# 2TinyISD1700_V2_2020-08-10-smd-sop.net
KiCad netlist of a schematic drawn in EAGLE
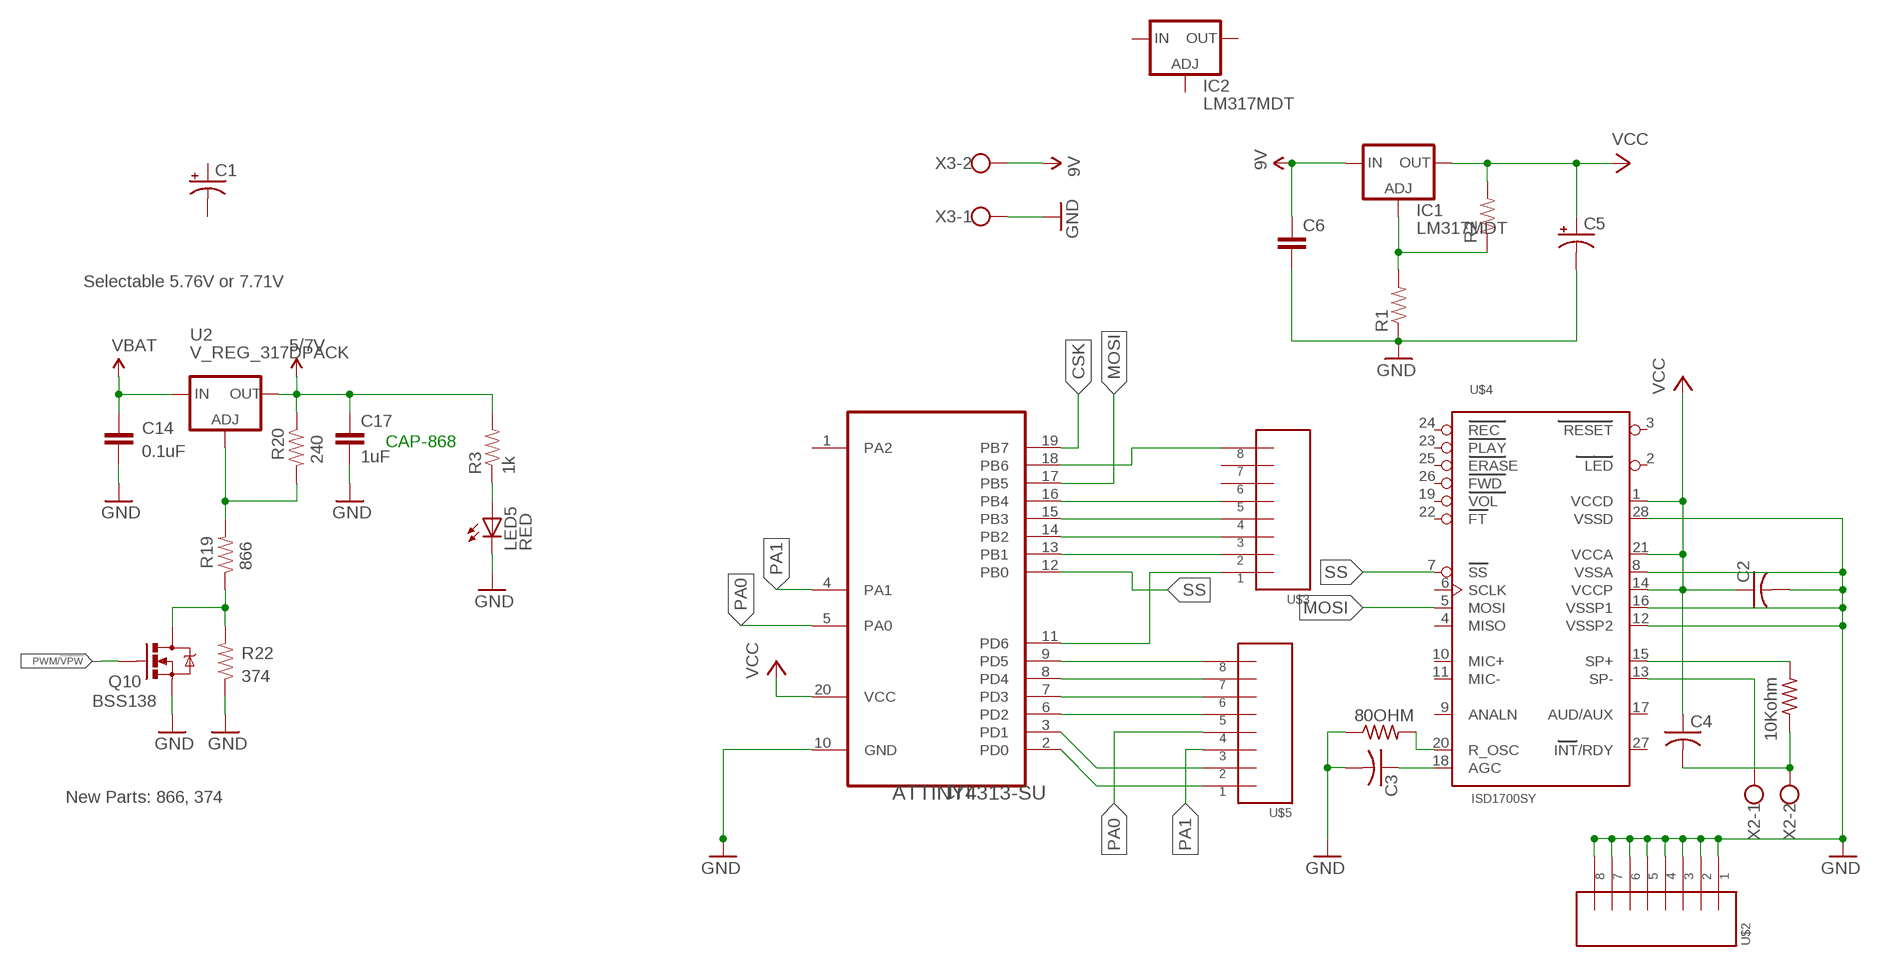
[diagram p0: schematic, sheet 1]

(export (version "E")
  (design (tool "Eeschema 10.0.6"))
  (components
    (comp (ref "80OHM")
      (value "R-US_0204/2V")
      (footprint "eagle-import:0204V")
      (libsource (lib "eagle-import") (part "R-US_0204/2V"))
    )
    (comp (ref "80OHM1")
      (value "10Kohm")
      (footprint "eagle-import:0204V")
      (libsource (lib "eagle-import") (part "R-US_0204/2V"))
    )
    (comp (ref "C1")
      (value "CAP_POL1206")
      (footprint "eagle-import:EIA3216")
      (libsource (lib "eagle-import") (part "CAP_POL1206"))
    )
    (comp (ref "C2")
      (value "C-US050-030X075")
      (footprint "eagle-import:C050-030X075")
      (libsource (lib "eagle-import") (part "C-US050-030X075"))
    )
    (comp (ref "C3")
      (value "C-US050-030X075")
      (footprint "eagle-import:C050-030X075")
      (libsource (lib "eagle-import") (part "C-US050-030X075"))
    )
    (comp (ref "C4")
      (value "C-US050-030X075")
      (footprint "eagle-import:C050-030X075")
      (libsource (lib "eagle-import") (part "C-US050-030X075"))
    )
    (comp (ref "C5")
      (value "CAP_POL1206")
      (footprint "eagle-import:EIA3216")
      (libsource (lib "eagle-import") (part "CAP_POL1206"))
    )
    (comp (ref "C6")
      (value "CAP0805")
      (footprint "eagle-import:0805")
      (libsource (lib "eagle-import") (part "SparkFun2_CAP0805"))
    )
    (comp (ref "C14")
      (value "0.1uF")
      (footprint "eagle-import:0402-CAP")
      (libsource (lib "eagle-import") (part "CAP0402-CAP"))
    )
    (comp (ref "C17")
      (value "1uF")
      (footprint "eagle-import:0402-CAP")
      (libsource (lib "eagle-import") (part "CAP0402-CAP"))
    )
    (comp (ref "IC1")
      (value "LM317MDT")
      (footprint "eagle-import:DPACK")
      (libsource (lib "eagle-import") (part "LM317?MDT"))
    )
    (comp (ref "IC2")
      (value "LM317MDT")
      (footprint "eagle-import:DPACK")
      (libsource (lib "eagle-import") (part "LM317?MDT"))
    )
    (comp (ref "LED5")
      (value "RED")
      (footprint "eagle-import:LED-0603")
      (libsource (lib "eagle-import") (part "LED0603"))
    )
    (comp (ref "Q10")
      (value "BSS138")
      (footprint "eagle-import:SOT23-3")
      (libsource (lib "eagle-import") (part "MOSFET-NCHANNELSMD"))
    )
    (comp (ref "R1")
      (value "RESISTOR")
      (footprint "eagle-import:0805")
      (libsource (lib "eagle-import") (part "RESISTOR"))
    )
    (comp (ref "R2")
      (value "RESISTOR")
      (footprint "eagle-import:0805")
      (libsource (lib "eagle-import") (part "RESISTOR"))
    )
    (comp (ref "R3")
      (value "1k")
      (footprint "eagle-import:0402-RES")
      (libsource (lib "eagle-import") (part "RESISTOR0402-RES"))
    )
    (comp (ref "R19")
      (value "866")
      (footprint "eagle-import:0402-RES")
      (libsource (lib "eagle-import") (part "RESISTOR0402-RES"))
    )
    (comp (ref "R20")
      (value "240")
      (footprint "eagle-import:0402-RES")
      (libsource (lib "eagle-import") (part "RESISTOR0402-RES"))
    )
    (comp (ref "R22")
      (value "374")
      (footprint "eagle-import:0402-RES")
      (libsource (lib "eagle-import") (part "RESISTOR0402-RES"))
    )
    (comp (ref "U$2")
      (value "8PIN_HEADER")
      (footprint "eagle-import:8PIN_HEADER")
      (fields (field (name "MF") "RENESAS") (field (name "MPN") "YSDKS128E10"))
      (libsource (lib "eagle-import") (part "8PIN_HEADER"))
    )
    (comp (ref "U$3")
      (value "8PIN_HEADER")
      (footprint "eagle-import:8PIN_HEADER")
      (fields (field (name "MF") "RENESAS") (field (name "MPN") "YSDKS128E10"))
      (libsource (lib "eagle-import") (part "8PIN_HEADER"))
    )
    (comp (ref "U$4")
      (value "ISD1700SY")
      (footprint "eagle-import:SO28W")
      (libsource (lib "eagle-import") (part "ISD1700SY"))
    )
    (comp (ref "U$5")
      (value "8PIN_HEADER")
      (footprint "eagle-import:8PIN_HEADER")
      (fields (field (name "MF") "RENESAS") (field (name "MPN") "YSDKS128E10"))
      (libsource (lib "eagle-import") (part "8PIN_HEADER"))
    )
    (comp (ref "U1")
      (value "ATTINY4313-SU")
      (footprint "eagle-import:SOIC127P1032X265-20N")
      (fields (field (name "MF") "MICROCHIP"))
      (libsource (lib "eagle-import") (part "ATTINY4313-SU"))
    )
    (comp (ref "U2")
      (value "V_REG_317DPACK")
      (footprint "eagle-import:V-REG_DPACK")
      (libsource (lib "eagle-import") (part "V_REG_317DPACK"))
    )
    (comp (ref "X2")
      (value "W237-102")
      (footprint "eagle-import:W237-102")
      (fields (field (name "MPN") "237-102"))
      (libsource (lib "eagle-import") (part "W237-102"))
    )
    (comp (ref "X3")
      (value "W237-102")
      (footprint "eagle-import:W237-102")
      (fields (field (name "MPN") "237-102") (field (name "OC_NEWARK") "70K9898"))
      (libsource (lib "eagle-import") (part "W237-102"))
    )
  )
  (nets
    (net (code "1") (name "/PWM{slash}~{VPW}") (class "Default")
      (node (ref "Q10") (pin "1") (pinfunction "G_1") (pintype "passive"))
    )
    (net (code "2") (name "5{slash}7V") (class "Default")
      (node (ref "C17") (pin "1") (pinfunction "1_1") (pintype "passive"))
      (node (ref "C2") (pin "1") (pinfunction "1_1") (pintype "passive"))
      (node (ref "C4") (pin "1") (pinfunction "1_1") (pintype "passive"))
      (node (ref "C5") (pin "A") (pinfunction "+_A") (pintype "passive"))
      (node (ref "IC1") (pin "4") (pinfunction "OUT_4") (pintype "passive"))
      (node (ref "R2") (pin "2") (pinfunction "2_2") (pintype "passive"))
      (node (ref "R20") (pin "1") (pinfunction "1_1") (pintype "passive"))
      (node (ref "R3") (pin "2") (pinfunction "2_2") (pintype "passive"))
      (node (ref "U$4") (pin "1") (pinfunction "VCCD_1") (pintype "power_in"))
      (node (ref "U$4") (pin "14") (pinfunction "VCCP_14") (pintype "power_in"))
      (node (ref "U$4") (pin "21") (pinfunction "VCCA_21") (pintype "power_in"))
      (node (ref "U1") (pin "20") (pinfunction "VCC_20") (pintype "power_in"))
      (node (ref "U2") (pin "4") (pinfunction "OUT_4") (pintype "output"))
    )
    (net (code "3") (name "9V") (class "Default")
      (node (ref "C6") (pin "1") (pinfunction "1_1") (pintype "passive"))
      (node (ref "IC1") (pin "3") (pinfunction "IN_3") (pintype "input"))
      (node (ref "X3") (pin "2") (pinfunction "KL_2") (pintype "passive"))
    )
    (net (code "4") (name "CSK") (class "Default")
      (node (ref "U1") (pin "19") (pinfunction "PB7_19") (pintype "bidirectional"))
    )
    (net (code "5") (name "GND") (class "Default")
      (node (ref "80OHM") (pin "1") (pinfunction "1_1") (pintype "passive"))
      (node (ref "C14") (pin "2") (pinfunction "2_2") (pintype "passive"))
      (node (ref "C17") (pin "2") (pinfunction "2_2") (pintype "passive"))
      (node (ref "C2") (pin "2") (pinfunction "2_2") (pintype "passive"))
      (node (ref "C3") (pin "2") (pinfunction "2_2") (pintype "passive"))
      (node (ref "C5") (pin "C") (pinfunction "-_C") (pintype "passive"))
      (node (ref "C6") (pin "2") (pinfunction "2_2") (pintype "passive"))
      (node (ref "LED5") (pin "C") (pinfunction "C_C") (pintype "passive"))
      (node (ref "Q10") (pin "2") (pinfunction "S_2") (pintype "passive"))
      (node (ref "R1") (pin "1") (pinfunction "1_1") (pintype "passive"))
      (node (ref "R22") (pin "1") (pinfunction "1_1") (pintype "passive"))
      (node (ref "U$2") (pin "P$1") (pinfunction "P$1_P$1") (pintype "bidirectional"))
      (node (ref "U$2") (pin "P$2") (pinfunction "P$2_P$2") (pintype "bidirectional"))
      (node (ref "U$2") (pin "P$3") (pinfunction "P$3_P$3") (pintype "bidirectional"))
      (node (ref "U$2") (pin "P$4") (pinfunction "P$4_P$4") (pintype "bidirectional"))
      (node (ref "U$2") (pin "P$5") (pinfunction "P$5_P$5") (pintype "bidirectional"))
      (node (ref "U$2") (pin "P$6") (pinfunction "P$6_P$6") (pintype "bidirectional"))
      (node (ref "U$2") (pin "P$7") (pinfunction "P$7_P$7") (pintype "bidirectional"))
      (node (ref "U$2") (pin "P$8") (pinfunction "P$8_P$8") (pintype "bidirectional"))
      (node (ref "U$4") (pin "12") (pinfunction "VSSP2_12") (pintype "power_in"))
      (node (ref "U$4") (pin "16") (pinfunction "VSSP1_16") (pintype "power_in"))
      (node (ref "U$4") (pin "28") (pinfunction "VSSD_28") (pintype "power_in"))
      (node (ref "U$4") (pin "8") (pinfunction "VSSA_8") (pintype "power_in"))
      (node (ref "U1") (pin "10") (pinfunction "GND_10") (pintype "passive"))
      (node (ref "X3") (pin "1") (pinfunction "KL_1") (pintype "passive"))
    )
    (net (code "6") (name "MOSI") (class "Default")
      (node (ref "U$4") (pin "5") (pinfunction "MOSI_5") (pintype "input"))
      (node (ref "U1") (pin "17") (pinfunction "PB5_17") (pintype "bidirectional"))
    )
    (net (code "7") (name "Net-(IC1-ADJ)") (class "Default")
      (node (ref "IC1") (pin "1") (pinfunction "ADJ_1") (pintype "input"))
      (node (ref "R1") (pin "2") (pinfunction "2_2") (pintype "passive"))
      (node (ref "R2") (pin "1") (pinfunction "1_1") (pintype "passive"))
    )
    (net (code "8") (name "Net-(LED5-PadA)") (class "Default")
      (node (ref "LED5") (pin "A") (pinfunction "A_A") (pintype "passive"))
      (node (ref "R3") (pin "1") (pinfunction "1_1") (pintype "passive"))
    )
    (net (code "9") (name "Net-(Q10-D)") (class "Default")
      (node (ref "Q10") (pin "3") (pinfunction "D_3") (pintype "passive"))
      (node (ref "R19") (pin "1") (pinfunction "1_1") (pintype "passive"))
      (node (ref "R22") (pin "2") (pinfunction "2_2") (pintype "passive"))
    )
    (net (code "10") (name "Net-(U$4-AGC)") (class "Default")
      (node (ref "C3") (pin "1") (pinfunction "1_1") (pintype "passive"))
      (node (ref "U$4") (pin "18") (pinfunction "AGC_18") (pintype "passive"))
    )
    (net (code "11") (name "Net-(U$4-R_OSC)") (class "Default")
      (node (ref "80OHM") (pin "2") (pinfunction "2_2") (pintype "passive"))
      (node (ref "U$4") (pin "20") (pinfunction "R_OSC_20") (pintype "passive"))
    )
    (net (code "12") (name "Net-(U$4-SP+)") (class "Default")
      (node (ref "80OHM1") (pin "2") (pinfunction "2_2") (pintype "passive"))
      (node (ref "U$4") (pin "15") (pinfunction "SP+_15") (pintype "output"))
    )
    (net (code "13") (name "Net-(U$4-SP-)") (class "Default")
      (node (ref "U$4") (pin "13") (pinfunction "SP-_13") (pintype "output"))
      (node (ref "X2") (pin "1") (pinfunction "KL_1") (pintype "passive"))
    )
    (net (code "14") (name "Net-(U1-PB1)") (class "Default")
      (node (ref "U$3") (pin "P$2") (pinfunction "P$2_P$2") (pintype "bidirectional"))
      (node (ref "U1") (pin "13") (pinfunction "PB1_13") (pintype "bidirectional"))
    )
    (net (code "15") (name "Net-(U1-PB2)") (class "Default")
      (node (ref "U$3") (pin "P$3") (pinfunction "P$3_P$3") (pintype "bidirectional"))
      (node (ref "U1") (pin "14") (pinfunction "PB2_14") (pintype "bidirectional"))
    )
    (net (code "16") (name "Net-(U1-PB3)") (class "Default")
      (node (ref "U$3") (pin "P$4") (pinfunction "P$4_P$4") (pintype "bidirectional"))
      (node (ref "U1") (pin "15") (pinfunction "PB3_15") (pintype "bidirectional"))
    )
    (net (code "17") (name "Net-(U1-PB4)") (class "Default")
      (node (ref "U$3") (pin "P$5") (pinfunction "P$5_P$5") (pintype "bidirectional"))
      (node (ref "U1") (pin "16") (pinfunction "PB4_16") (pintype "bidirectional"))
    )
    (net (code "18") (name "Net-(U1-PB6)") (class "Default")
      (node (ref "U$3") (pin "P$8") (pinfunction "P$8_P$8") (pintype "bidirectional"))
      (node (ref "U1") (pin "18") (pinfunction "PB6_18") (pintype "bidirectional"))
    )
    (net (code "19") (name "Net-(U1-PD0)") (class "Default")
      (node (ref "U$5") (pin "P$1") (pinfunction "P$1_P$1") (pintype "bidirectional"))
      (node (ref "U1") (pin "2") (pinfunction "PD0_2") (pintype "bidirectional"))
    )
    (net (code "20") (name "Net-(U1-PD1)") (class "Default")
      (node (ref "U$5") (pin "P$2") (pinfunction "P$2_P$2") (pintype "bidirectional"))
      (node (ref "U1") (pin "3") (pinfunction "PD1_3") (pintype "bidirectional"))
    )
    (net (code "21") (name "Net-(U1-PD2)") (class "Default")
      (node (ref "U$5") (pin "P$5") (pinfunction "P$5_P$5") (pintype "bidirectional"))
      (node (ref "U1") (pin "6") (pinfunction "PD2_6") (pintype "bidirectional"))
    )
    (net (code "22") (name "Net-(U1-PD3)") (class "Default")
      (node (ref "U$5") (pin "P$6") (pinfunction "P$6_P$6") (pintype "bidirectional"))
      (node (ref "U1") (pin "7") (pinfunction "PD3_7") (pintype "bidirectional"))
    )
    (net (code "23") (name "Net-(U1-PD4)") (class "Default")
      (node (ref "U$5") (pin "P$7") (pinfunction "P$7_P$7") (pintype "bidirectional"))
      (node (ref "U1") (pin "8") (pinfunction "PD4_8") (pintype "bidirectional"))
    )
    (net (code "24") (name "Net-(U1-PD5)") (class "Default")
      (node (ref "U$5") (pin "P$8") (pinfunction "P$8_P$8") (pintype "bidirectional"))
      (node (ref "U1") (pin "9") (pinfunction "PD5_9") (pintype "bidirectional"))
    )
    (net (code "25") (name "Net-(U1-PD6)") (class "Default")
      (node (ref "U$3") (pin "P$1") (pinfunction "P$1_P$1") (pintype "bidirectional"))
      (node (ref "U1") (pin "11") (pinfunction "PD6_11") (pintype "bidirectional"))
    )
    (net (code "26") (name "Net-(U2-ADJ)") (class "Default")
      (node (ref "R19") (pin "2") (pinfunction "2_2") (pintype "passive"))
      (node (ref "R20") (pin "2") (pinfunction "2_2") (pintype "passive"))
      (node (ref "U2") (pin "1") (pinfunction "ADJ_1") (pintype "input"))
    )
    (net (code "27") (name "Net-(X2B-KL)") (class "Default")
      (node (ref "80OHM1") (pin "1") (pinfunction "1_1") (pintype "passive"))
      (node (ref "C4") (pin "2") (pinfunction "2_2") (pintype "passive"))
      (node (ref "X2") (pin "2") (pinfunction "KL_2") (pintype "passive"))
    )
    (net (code "28") (name "PA0") (class "Default")
      (node (ref "U$5") (pin "P$4") (pinfunction "P$4_P$4") (pintype "bidirectional"))
      (node (ref "U1") (pin "5") (pinfunction "PA0_5") (pintype "bidirectional"))
    )
    (net (code "29") (name "PA1") (class "Default")
      (node (ref "U$5") (pin "P$3") (pinfunction "P$3_P$3") (pintype "bidirectional"))
      (node (ref "U1") (pin "4") (pinfunction "PA1_4") (pintype "bidirectional"))
    )
    (net (code "30") (name "SS") (class "Default")
      (node (ref "U$4") (pin "7") (pinfunction "SS_7") (pintype "input"))
      (node (ref "U1") (pin "12") (pinfunction "PB0_12") (pintype "bidirectional"))
    )
    (net (code "31") (name "VBAT") (class "Default")
      (node (ref "C14") (pin "1") (pinfunction "1_1") (pintype "passive"))
      (node (ref "U2") (pin "3") (pinfunction "IN_3") (pintype "input"))
    )
    (net (code "32") (name "unconnected-(C1-+-PadA)") (class "Default")
      (node (ref "C1") (pin "A") (pinfunction "+_A") (pintype "passive"))
    )
    (net (code "33") (name "unconnected-(C1---PadC)") (class "Default")
      (node (ref "C1") (pin "C") (pinfunction "-_C") (pintype "passive"))
    )
    (net (code "34") (name "unconnected-(IC2-ADJ-Pad1)") (class "Default")
      (node (ref "IC2") (pin "1") (pinfunction "ADJ_1") (pintype "input"))
    )
    (net (code "35") (name "unconnected-(IC2-IN-Pad3)") (class "Default")
      (node (ref "IC2") (pin "3") (pinfunction "IN_3") (pintype "input"))
    )
    (net (code "36") (name "unconnected-(IC2-OUT-Pad4)") (class "Default")
      (node (ref "IC2") (pin "4") (pinfunction "OUT_4") (pintype "passive"))
    )
    (net (code "37") (name "unconnected-(U$3-PadP$6)") (class "Default")
      (node (ref "U$3") (pin "P$6") (pinfunction "P$6_P$6") (pintype "bidirectional"))
    )
    (net (code "38") (name "unconnected-(U$3-PadP$7)") (class "Default")
      (node (ref "U$3") (pin "P$7") (pinfunction "P$7_P$7") (pintype "bidirectional"))
    )
    (net (code "39") (name "unconnected-(U$4-ANALN-Pad9)") (class "Default")
      (node (ref "U$4") (pin "9") (pinfunction "ANALN_9") (pintype "input"))
    )
    (net (code "40") (name "unconnected-(U$4-AUD{slash}AUX-Pad17)") (class "Default")
      (node (ref "U$4") (pin "17") (pinfunction "AUD/AUX_17") (pintype "output"))
    )
    (net (code "41") (name "unconnected-(U$4-ERASE-Pad25)") (class "Default")
      (node (ref "U$4") (pin "25") (pinfunction "ERASE_25") (pintype "input"))
    )
    (net (code "42") (name "unconnected-(U$4-FT-Pad22)") (class "Default")
      (node (ref "U$4") (pin "22") (pinfunction "FT_22") (pintype "input"))
    )
    (net (code "43") (name "unconnected-(U$4-FWD-Pad26)") (class "Default")
      (node (ref "U$4") (pin "26") (pinfunction "FWD_26") (pintype "input"))
    )
    (net (code "44") (name "unconnected-(U$4-INT{slash}RDY-Pad27)") (class "Default")
      (node (ref "U$4") (pin "27") (pinfunction "INT/RDY_27") (pintype "bidirectional"))
    )
    (net (code "45") (name "unconnected-(U$4-LED-Pad2)") (class "Default")
      (node (ref "U$4") (pin "2") (pinfunction "LED_2") (pintype "input"))
    )
    (net (code "46") (name "unconnected-(U$4-MIC+-Pad10)") (class "Default")
      (node (ref "U$4") (pin "10") (pinfunction "MIC+_10") (pintype "input"))
    )
    (net (code "47") (name "unconnected-(U$4-MIC--Pad11)") (class "Default")
      (node (ref "U$4") (pin "11") (pinfunction "MIC-_11") (pintype "input"))
    )
    (net (code "48") (name "unconnected-(U$4-MISO-Pad4)") (class "Default")
      (node (ref "U$4") (pin "4") (pinfunction "MISO_4") (pintype "input"))
    )
    (net (code "49") (name "unconnected-(U$4-PLAY-Pad23)") (class "Default")
      (node (ref "U$4") (pin "23") (pinfunction "PLAY_23") (pintype "input"))
    )
    (net (code "50") (name "unconnected-(U$4-REC-Pad24)") (class "Default")
      (node (ref "U$4") (pin "24") (pinfunction "REC_24") (pintype "input"))
    )
    (net (code "51") (name "unconnected-(U$4-RESET-Pad3)") (class "Default")
      (node (ref "U$4") (pin "3") (pinfunction "RESET_3") (pintype "input"))
    )
    (net (code "52") (name "unconnected-(U$4-SCLK-Pad6)") (class "Default")
      (node (ref "U$4") (pin "6") (pinfunction "SCLK_6") (pintype "input"))
    )
    (net (code "53") (name "unconnected-(U$4-VOL-Pad19)") (class "Default")
      (node (ref "U$4") (pin "19") (pinfunction "VOL_19") (pintype "input"))
    )
    (net (code "54") (name "unconnected-(U1-PA2-Pad1)") (class "Default")
      (node (ref "U1") (pin "1") (pinfunction "PA2_1") (pintype "bidirectional"))
    )
  )
)
